# Smart_Mic_V01.net
KiCad netlist of a schematic drawn in EAGLE
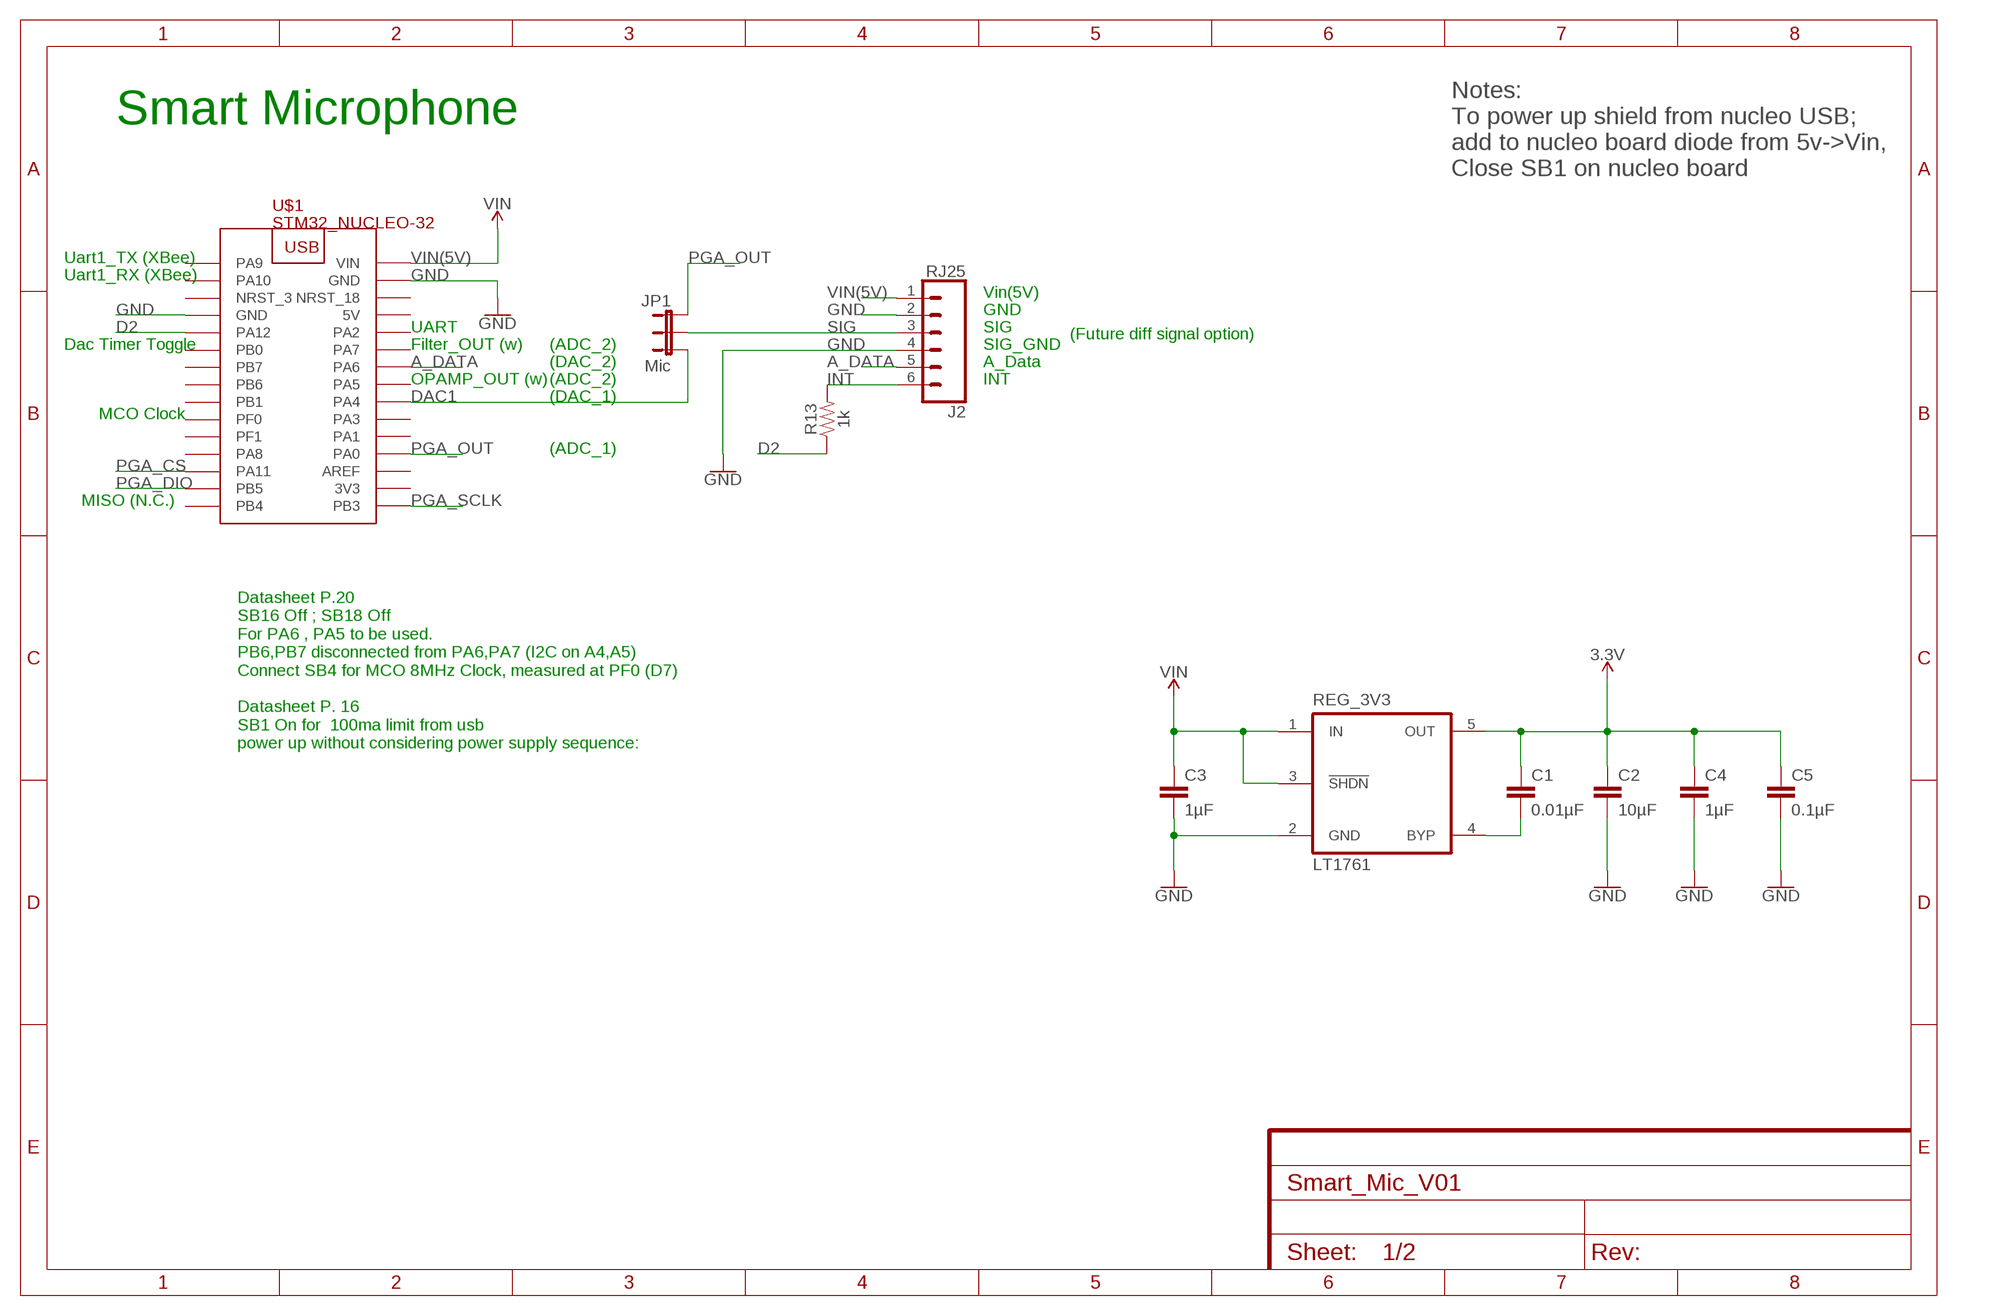
[diagram p0: schematic, sheet 1]
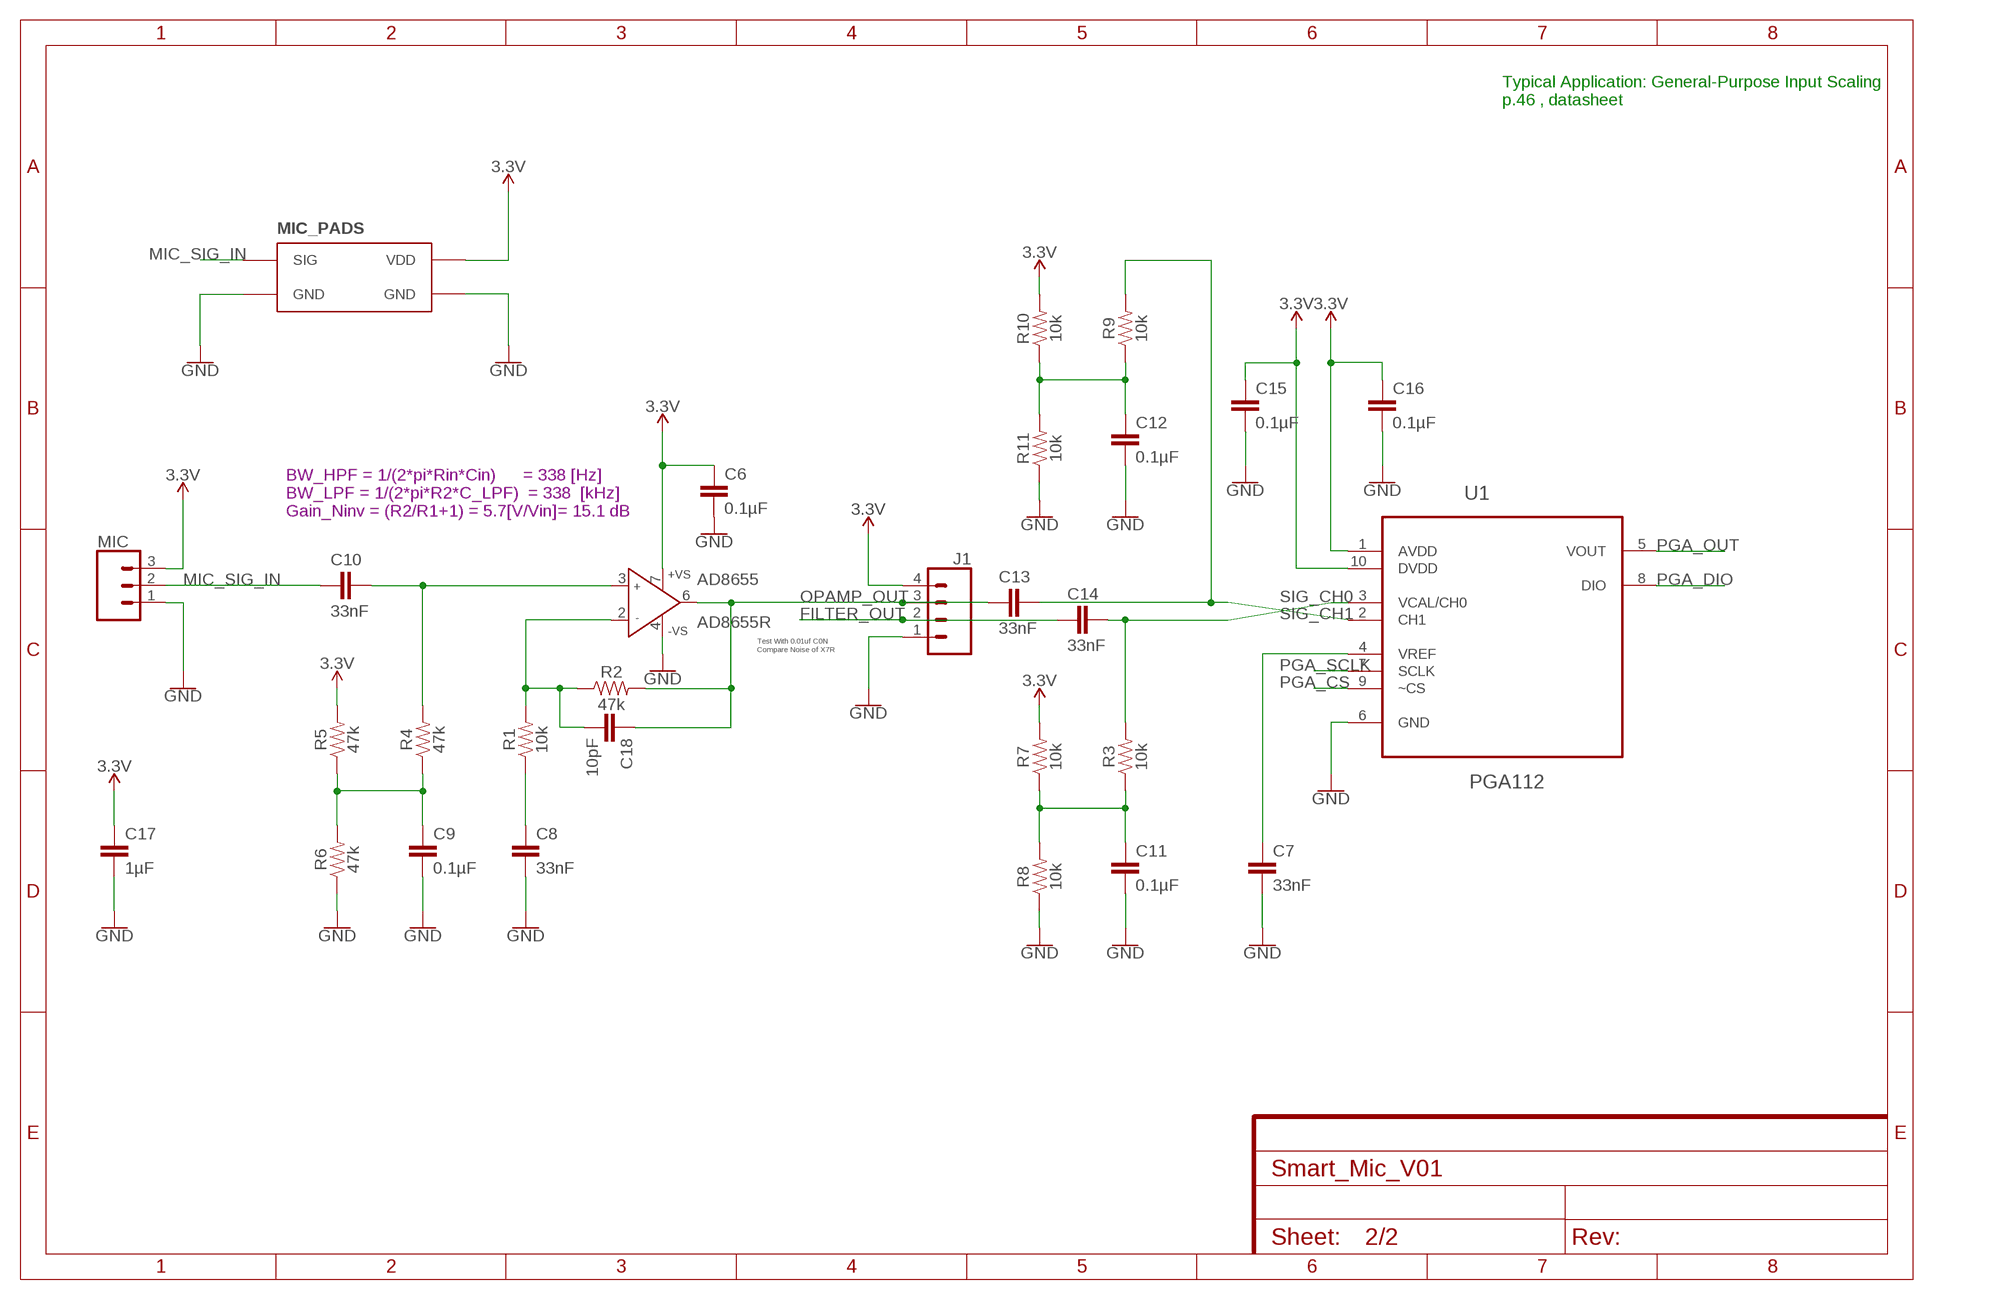
[diagram p1: schematic, sheet 2]

(export (version "E")
  (design (tool "Eeschema 10.0.6"))
  (components
    (comp (ref "C1")
      (value "0.01µF")
      (footprint "eagle-import:0805")
      (libsource (lib "eagle-import") (part "0.33UF/330NF-0805-50V-10%"))
    )
    (comp (ref "C2")
      (value "10µF")
      (footprint "eagle-import:0805")
      (libsource (lib "eagle-import") (part "0.33UF/330NF-0805-50V-10%"))
    )
    (comp (ref "C3")
      (value "1µF")
      (footprint "eagle-import:0805")
      (libsource (lib "eagle-import") (part "0.33UF/330NF-0805-50V-10%"))
    )
    (comp (ref "C4")
      (value "1µF")
      (footprint "eagle-import:0805")
      (libsource (lib "eagle-import") (part "0.33UF/330NF-0805-50V-10%"))
    )
    (comp (ref "C5")
      (value "0.1µF")
      (footprint "eagle-import:0805")
      (libsource (lib "eagle-import") (part "0.33UF/330NF-0805-50V-10%"))
    )
    (comp (ref "J2")
      (value "RJ25")
      (footprint "eagle-import:RJ11-6")
      (libsource (lib "eagle-import") (part "RJ11-6"))
    )
    (comp (ref "JP1")
      (value "Mic")
      (footprint "eagle-import:1X03")
      (libsource (lib "eagle-import") (part "JUMPER-3PTH"))
    )
    (comp (ref "R13")
      (value "1k")
      (footprint "eagle-import:0805")
      (libsource (lib "eagle-import") (part "RESISTOR0805"))
    )
    (comp (ref "REG_3V3")
      (value "LT1761")
      (footprint "eagle-import:SOT23-5")
      (libsource (lib "eagle-import") (part "LT1761"))
    )
    (comp (ref "U$1")
      (value "STM32_NUCLEO-32")
      (footprint "eagle-import:STM32_NUCLEO-32")
      (libsource (lib "eagle-import") (part "STM32_NUCLEO-32"))
    )
    (comp (ref "AD8655")
      (value "AD8655R")
      (footprint "eagle-import:SO8")
      (fields (field (name "MF") "ALTERA CORPORATION") (field (name "MPN") "AD8655ARMZ-REEL"))
      (libsource (lib "eagle-import") (part "AD8655R"))
    )
    (comp (ref "C6")
      (value "0.1µF")
      (footprint "eagle-import:0805")
      (libsource (lib "eagle-import") (part "0.33UF/330NF-0805-50V-10%"))
    )
    (comp (ref "C7")
      (value "33nF")
      (footprint "eagle-import:0805")
      (libsource (lib "eagle-import") (part "0.33UF/330NF-0805-50V-10%"))
    )
    (comp (ref "C8")
      (value "33nF")
      (footprint "eagle-import:0805")
      (libsource (lib "eagle-import") (part "0.33UF/330NF-0805-50V-10%"))
    )
    (comp (ref "C9")
      (value "0.1µF")
      (footprint "eagle-import:0805")
      (libsource (lib "eagle-import") (part "0.33UF/330NF-0805-50V-10%"))
    )
    (comp (ref "C10")
      (value "33nF")
      (footprint "eagle-import:0805")
      (libsource (lib "eagle-import") (part "0.33UF/330NF-0805-50V-10%"))
    )
    (comp (ref "C11")
      (value "0.1µF")
      (footprint "eagle-import:0805")
      (libsource (lib "eagle-import") (part "0.33UF/330NF-0805-50V-10%"))
    )
    (comp (ref "C12")
      (value "0.1µF")
      (footprint "eagle-import:0805")
      (libsource (lib "eagle-import") (part "0.33UF/330NF-0805-50V-10%"))
    )
    (comp (ref "C13")
      (value "33nF")
      (footprint "eagle-import:0805")
      (libsource (lib "eagle-import") (part "0.33UF/330NF-0805-50V-10%"))
    )
    (comp (ref "C14")
      (value "33nF")
      (footprint "eagle-import:0805")
      (libsource (lib "eagle-import") (part "0.33UF/330NF-0805-50V-10%"))
    )
    (comp (ref "C15")
      (value "0.1µF")
      (footprint "eagle-import:0805")
      (libsource (lib "eagle-import") (part "0.33UF/330NF-0805-50V-10%"))
    )
    (comp (ref "C16")
      (value "0.1µF")
      (footprint "eagle-import:0805")
      (libsource (lib "eagle-import") (part "0.33UF/330NF-0805-50V-10%"))
    )
    (comp (ref "C17")
      (value "1µF")
      (footprint "eagle-import:0805")
      (libsource (lib "eagle-import") (part "0.33UF/330NF-0805-50V-10%"))
    )
    (comp (ref "C18")
      (value "10pF")
      (footprint "eagle-import:0805")
      (libsource (lib "eagle-import") (part "0.33UF/330NF-0805-50V-10%"))
    )
    (comp (ref "J1")
      (value "CONN_04")
      (footprint "eagle-import:1X04")
      (libsource (lib "eagle-import") (part "CONN_04"))
    )
    (comp (ref "MIC")
      (value "CONN_03")
      (footprint "eagle-import:1X03")
      (libsource (lib "eagle-import") (part "CONN_03"))
    )
    (comp (ref "R1")
      (value "10k")
      (footprint "eagle-import:0805")
      (libsource (lib "eagle-import") (part "RESISTOR0805"))
    )
    (comp (ref "R2")
      (value "47k")
      (footprint "eagle-import:0805")
      (libsource (lib "eagle-import") (part "RESISTOR0805"))
    )
    (comp (ref "R3")
      (value "10k")
      (footprint "eagle-import:0805")
      (libsource (lib "eagle-import") (part "RESISTOR0805"))
    )
    (comp (ref "R4")
      (value "47k")
      (footprint "eagle-import:0805")
      (libsource (lib "eagle-import") (part "RESISTOR0805"))
    )
    (comp (ref "R5")
      (value "47k")
      (footprint "eagle-import:0805")
      (libsource (lib "eagle-import") (part "RESISTOR0805"))
    )
    (comp (ref "R6")
      (value "47k")
      (footprint "eagle-import:0805")
      (libsource (lib "eagle-import") (part "RESISTOR0805"))
    )
    (comp (ref "R7")
      (value "10k")
      (footprint "eagle-import:0805")
      (libsource (lib "eagle-import") (part "RESISTOR0805"))
    )
    (comp (ref "R8")
      (value "10k")
      (footprint "eagle-import:0805")
      (libsource (lib "eagle-import") (part "RESISTOR0805"))
    )
    (comp (ref "R9")
      (value "10k")
      (footprint "eagle-import:0805")
      (libsource (lib "eagle-import") (part "RESISTOR0805"))
    )
    (comp (ref "R10")
      (value "10k")
      (footprint "eagle-import:0805")
      (libsource (lib "eagle-import") (part "RESISTOR0805"))
    )
    (comp (ref "R11")
      (value "10k")
      (footprint "eagle-import:0805")
      (libsource (lib "eagle-import") (part "RESISTOR0805"))
    )
    (comp (ref "U$2")
      (value "MIC_PADS")
      (footprint "eagle-import:MIC_PADS")
      (libsource (lib "eagle-import") (part "MIC_PADS"))
    )
    (comp (ref "U1")
      (value "PGA112")
      (footprint "eagle-import:SOP50P490X110-10N")
      (fields (field (name "MPN") "PGA113AIDGST"))
      (libsource (lib "eagle-import") (part "PGA113AIDGST"))
    )
  )
  (nets
    (net (code "1") (name "3.3V") (class "Default")
      (node (ref "AD8655") (pin "7") (pinfunction "+VS_7") (pintype "input"))
      (node (ref "C1") (pin "1") (pinfunction "1_1") (pintype "passive"))
      (node (ref "C15") (pin "1") (pinfunction "1_1") (pintype "passive"))
      (node (ref "C16") (pin "1") (pinfunction "1_1") (pintype "passive"))
      (node (ref "C17") (pin "1") (pinfunction "1_1") (pintype "passive"))
      (node (ref "C2") (pin "1") (pinfunction "1_1") (pintype "passive"))
      (node (ref "C4") (pin "1") (pinfunction "1_1") (pintype "passive"))
      (node (ref "C5") (pin "1") (pinfunction "1_1") (pintype "passive"))
      (node (ref "C6") (pin "1") (pinfunction "1_1") (pintype "passive"))
      (node (ref "J1") (pin "4") (pinfunction "4_4") (pintype "passive"))
      (node (ref "MIC") (pin "3") (pinfunction "3_3") (pintype "passive"))
      (node (ref "R10") (pin "2") (pinfunction "2_2") (pintype "passive"))
      (node (ref "R5") (pin "2") (pinfunction "2_2") (pintype "passive"))
      (node (ref "R7") (pin "2") (pinfunction "2_2") (pintype "passive"))
      (node (ref "REG_3V3") (pin "5") (pinfunction "OUT_5") (pintype "bidirectional"))
      (node (ref "U$2") (pin "VDD") (pinfunction "VDD_VDD") (pintype "bidirectional"))
      (node (ref "U1") (pin "1") (pinfunction "AVDD_1") (pintype "power_in"))
      (node (ref "U1") (pin "10") (pinfunction "DVDD_10") (pintype "power_in"))
    )
    (net (code "2") (name "3V3") (class "Default")
      (node (ref "U$1") (pin "3V3") (pinfunction "3V3_3V3") (pintype "power_in"))
    )
    (net (code "3") (name "5V") (class "Default")
      (node (ref "U$1") (pin "5V") (pinfunction "5V_5V") (pintype "power_in"))
    )
    (net (code "4") (name "A_DATA") (class "Default")
      (node (ref "J2") (pin "5") (pinfunction "5_5") (pintype "passive"))
      (node (ref "U$1") (pin "PA6") (pinfunction "PA6_PA6") (pintype "bidirectional"))
    )
    (net (code "5") (name "D2") (class "Default")
      (node (ref "R13") (pin "1") (pinfunction "1_1") (pintype "passive"))
      (node (ref "U$1") (pin "PA12") (pinfunction "PA12_PA12") (pintype "bidirectional"))
    )
    (net (code "6") (name "DAC1") (class "Default")
      (node (ref "JP1") (pin "3") (pinfunction "3_3") (pintype "passive"))
      (node (ref "U$1") (pin "PA4") (pinfunction "PA4_PA4") (pintype "bidirectional"))
    )
    (net (code "7") (name "FILTER_OUT") (class "Default")
      (node (ref "C14") (pin "2") (pinfunction "2_2") (pintype "passive"))
      (node (ref "J1") (pin "2") (pinfunction "2_2") (pintype "passive"))
    )
    (net (code "8") (name "GND") (class "Default")
      (node (ref "AD8655") (pin "4") (pinfunction "-VS_4") (pintype "input"))
      (node (ref "C11") (pin "2") (pinfunction "2_2") (pintype "passive"))
      (node (ref "C12") (pin "2") (pinfunction "2_2") (pintype "passive"))
      (node (ref "C15") (pin "2") (pinfunction "2_2") (pintype "passive"))
      (node (ref "C16") (pin "2") (pinfunction "2_2") (pintype "passive"))
      (node (ref "C17") (pin "2") (pinfunction "2_2") (pintype "passive"))
      (node (ref "C2") (pin "2") (pinfunction "2_2") (pintype "passive"))
      (node (ref "C3") (pin "2") (pinfunction "2_2") (pintype "passive"))
      (node (ref "C4") (pin "2") (pinfunction "2_2") (pintype "passive"))
      (node (ref "C5") (pin "2") (pinfunction "2_2") (pintype "passive"))
      (node (ref "C6") (pin "2") (pinfunction "2_2") (pintype "passive"))
      (node (ref "C7") (pin "2") (pinfunction "2_2") (pintype "passive"))
      (node (ref "C8") (pin "2") (pinfunction "2_2") (pintype "passive"))
      (node (ref "C9") (pin "2") (pinfunction "2_2") (pintype "passive"))
      (node (ref "J1") (pin "1") (pinfunction "1_1") (pintype "passive"))
      (node (ref "J2") (pin "2") (pinfunction "2_2") (pintype "passive"))
      (node (ref "J2") (pin "4") (pinfunction "4_4") (pintype "passive"))
      (node (ref "MIC") (pin "1") (pinfunction "1_1") (pintype "passive"))
      (node (ref "R11") (pin "1") (pinfunction "1_1") (pintype "passive"))
      (node (ref "R6") (pin "1") (pinfunction "1_1") (pintype "passive"))
      (node (ref "R8") (pin "1") (pinfunction "1_1") (pintype "passive"))
      (node (ref "REG_3V3") (pin "2") (pinfunction "GND_2") (pintype "bidirectional"))
      (node (ref "U$1") (pin "GND@17") (pinfunction "GND_GND@17") (pintype "power_in"))
      (node (ref "U$1") (pin "GND@4") (pinfunction "GND_GND@4") (pintype "power_in"))
      (node (ref "U$2") (pin "GND$2") (pinfunction "GND_GND$2") (pintype "bidirectional"))
      (node (ref "U$2") (pin "GND$4") (pinfunction "GND_GND$4") (pintype "bidirectional"))
      (node (ref "U1") (pin "6") (pinfunction "GND_6") (pintype "passive"))
    )
    (net (code "9") (name "INT") (class "Default")
      (node (ref "J2") (pin "6") (pinfunction "6_6") (pintype "passive"))
      (node (ref "R13") (pin "2") (pinfunction "2_2") (pintype "passive"))
    )
    (net (code "10") (name "MIC_SIG_IN") (class "Default")
      (node (ref "C10") (pin "2") (pinfunction "2_2") (pintype "passive"))
      (node (ref "MIC") (pin "2") (pinfunction "2_2") (pintype "passive"))
      (node (ref "U$2") (pin "SIG") (pinfunction "SIG_SIG") (pintype "bidirectional"))
    )
    (net (code "11") (name "Net-(AD8655-IN+)") (class "Default")
      (node (ref "AD8655") (pin "3") (pinfunction "IN+_3") (pintype "input"))
      (node (ref "C10") (pin "1") (pinfunction "1_1") (pintype "passive"))
      (node (ref "R4") (pin "2") (pinfunction "2_2") (pintype "passive"))
    )
    (net (code "12") (name "Net-(AD8655-IN-)") (class "Default")
      (node (ref "AD8655") (pin "2") (pinfunction "IN-_2") (pintype "input"))
      (node (ref "C18") (pin "2") (pinfunction "2_2") (pintype "passive"))
      (node (ref "R1") (pin "2") (pinfunction "2_2") (pintype "passive"))
      (node (ref "R2") (pin "1") (pinfunction "1_1") (pintype "passive"))
    )
    (net (code "13") (name "Net-(C8-Pad1)") (class "Default")
      (node (ref "C8") (pin "1") (pinfunction "1_1") (pintype "passive"))
      (node (ref "R1") (pin "1") (pinfunction "1_1") (pintype "passive"))
    )
    (net (code "14") (name "Net-(C9-Pad1)") (class "Default")
      (node (ref "C9") (pin "1") (pinfunction "1_1") (pintype "passive"))
      (node (ref "R4") (pin "1") (pinfunction "1_1") (pintype "passive"))
      (node (ref "R5") (pin "1") (pinfunction "1_1") (pintype "passive"))
      (node (ref "R6") (pin "2") (pinfunction "2_2") (pintype "passive"))
    )
    (net (code "15") (name "Net-(C11-Pad1)") (class "Default")
      (node (ref "C11") (pin "1") (pinfunction "1_1") (pintype "passive"))
      (node (ref "R3") (pin "1") (pinfunction "1_1") (pintype "passive"))
      (node (ref "R7") (pin "1") (pinfunction "1_1") (pintype "passive"))
      (node (ref "R8") (pin "2") (pinfunction "2_2") (pintype "passive"))
    )
    (net (code "16") (name "Net-(C12-Pad1)") (class "Default")
      (node (ref "C12") (pin "1") (pinfunction "1_1") (pintype "passive"))
      (node (ref "R10") (pin "1") (pinfunction "1_1") (pintype "passive"))
      (node (ref "R11") (pin "2") (pinfunction "2_2") (pintype "passive"))
      (node (ref "R9") (pin "1") (pinfunction "1_1") (pintype "passive"))
    )
    (net (code "17") (name "Net-(REG_3V3-BYP)") (class "Default")
      (node (ref "C1") (pin "2") (pinfunction "2_2") (pintype "passive"))
      (node (ref "REG_3V3") (pin "4") (pinfunction "BYP_4") (pintype "bidirectional"))
    )
    (net (code "18") (name "Net-(U1-VREF)") (class "Default")
      (node (ref "C7") (pin "1") (pinfunction "1_1") (pintype "passive"))
      (node (ref "U1") (pin "4") (pinfunction "VREF_4") (pintype "input"))
    )
    (net (code "19") (name "OPAMP_OUT") (class "Default")
      (node (ref "AD8655") (pin "6") (pinfunction "OUT_6") (pintype "output"))
      (node (ref "C13") (pin "2") (pinfunction "2_2") (pintype "passive"))
      (node (ref "C18") (pin "1") (pinfunction "1_1") (pintype "passive"))
      (node (ref "J1") (pin "3") (pinfunction "3_3") (pintype "passive"))
      (node (ref "R2") (pin "2") (pinfunction "2_2") (pintype "passive"))
    )
    (net (code "20") (name "PGA_CS") (class "Default")
      (node (ref "U$1") (pin "PA11") (pinfunction "PA11_PA11") (pintype "bidirectional"))
      (node (ref "U1") (pin "9") (pinfunction "~{CS}_9") (pintype "input"))
    )
    (net (code "21") (name "PGA_DIO") (class "Default")
      (node (ref "U$1") (pin "PB5") (pinfunction "PB5_PB5") (pintype "bidirectional"))
      (node (ref "U1") (pin "8") (pinfunction "DIO_8") (pintype "bidirectional"))
    )
    (net (code "22") (name "PGA_OUT") (class "Default")
      (node (ref "JP1") (pin "1") (pinfunction "1_1") (pintype "passive"))
      (node (ref "U$1") (pin "PA0") (pinfunction "PA0_PA0") (pintype "bidirectional"))
      (node (ref "U1") (pin "5") (pinfunction "VOUT_5") (pintype "output"))
    )
    (net (code "23") (name "PGA_SCLK") (class "Default")
      (node (ref "U$1") (pin "PB3") (pinfunction "PB3_PB3") (pintype "bidirectional"))
      (node (ref "U1") (pin "7") (pinfunction "SCLK_7") (pintype "input"))
    )
    (net (code "24") (name "SIG") (class "Default")
      (node (ref "J2") (pin "3") (pinfunction "3_3") (pintype "passive"))
      (node (ref "JP1") (pin "2") (pinfunction "2_2") (pintype "passive"))
    )
    (net (code "25") (name "SIG_CH0") (class "Default")
      (node (ref "C13") (pin "1") (pinfunction "1_1") (pintype "passive"))
      (node (ref "R9") (pin "2") (pinfunction "2_2") (pintype "passive"))
      (node (ref "U1") (pin "2") (pinfunction "CH1_2") (pintype "input"))
    )
    (net (code "26") (name "SIG_CH1") (class "Default")
      (node (ref "C14") (pin "1") (pinfunction "1_1") (pintype "passive"))
      (node (ref "R3") (pin "2") (pinfunction "2_2") (pintype "passive"))
      (node (ref "U1") (pin "3") (pinfunction "VCAL/CH0_3") (pintype "input"))
    )
    (net (code "27") (name "VIN(5V)") (class "Default")
      (node (ref "C3") (pin "1") (pinfunction "1_1") (pintype "passive"))
      (node (ref "J2") (pin "1") (pinfunction "1_1") (pintype "passive"))
      (node (ref "REG_3V3") (pin "1") (pinfunction "IN_1") (pintype "bidirectional"))
      (node (ref "REG_3V3") (pin "3") (pinfunction "~{SHDN}_3") (pintype "bidirectional"))
      (node (ref "U$1") (pin "VIN") (pinfunction "VIN_VIN") (pintype "power_in"))
    )
    (net (code "28") (name "unconnected-(U$1-PadAREF)") (class "Default")
      (node (ref "U$1") (pin "AREF") (pinfunction "AREF_AREF") (pintype "bidirectional"))
    )
    (net (code "29") (name "unconnected-(U$1-PadNRST_3)") (class "Default")
      (node (ref "U$1") (pin "NRST_3") (pinfunction "NRST_3_NRST_3") (pintype "bidirectional"))
    )
    (net (code "30") (name "unconnected-(U$1-PadNRST_18)") (class "Default")
      (node (ref "U$1") (pin "NRST_18") (pinfunction "NRST_18_NRST_18") (pintype "bidirectional"))
    )
    (net (code "31") (name "unconnected-(U$1-PadPA1)") (class "Default")
      (node (ref "U$1") (pin "PA1") (pinfunction "PA1_PA1") (pintype "bidirectional"))
    )
    (net (code "32") (name "unconnected-(U$1-PadPA2)") (class "Default")
      (node (ref "U$1") (pin "PA2") (pinfunction "PA2_PA2") (pintype "bidirectional"))
    )
    (net (code "33") (name "unconnected-(U$1-PadPA3)") (class "Default")
      (node (ref "U$1") (pin "PA3") (pinfunction "PA3_PA3") (pintype "bidirectional"))
    )
    (net (code "34") (name "unconnected-(U$1-PadPA5)") (class "Default")
      (node (ref "U$1") (pin "PA5") (pinfunction "PA5_PA5") (pintype "bidirectional"))
    )
    (net (code "35") (name "unconnected-(U$1-PadPA7)") (class "Default")
      (node (ref "U$1") (pin "PA7") (pinfunction "PA7_PA7") (pintype "bidirectional"))
    )
    (net (code "36") (name "unconnected-(U$1-PadPA8)") (class "Default")
      (node (ref "U$1") (pin "PA8") (pinfunction "PA8_PA8") (pintype "bidirectional"))
    )
    (net (code "37") (name "unconnected-(U$1-PadPA9)") (class "Default")
      (node (ref "U$1") (pin "PA9") (pinfunction "PA9_PA9") (pintype "bidirectional"))
    )
    (net (code "38") (name "unconnected-(U$1-PadPA10)") (class "Default")
      (node (ref "U$1") (pin "PA10") (pinfunction "PA10_PA10") (pintype "bidirectional"))
    )
    (net (code "39") (name "unconnected-(U$1-PadPB0)") (class "Default")
      (node (ref "U$1") (pin "PB0") (pinfunction "PB0_PB0") (pintype "bidirectional"))
    )
    (net (code "40") (name "unconnected-(U$1-PadPB1)") (class "Default")
      (node (ref "U$1") (pin "PB1") (pinfunction "PB1_PB1") (pintype "bidirectional"))
    )
    (net (code "41") (name "unconnected-(U$1-PadPB4)") (class "Default")
      (node (ref "U$1") (pin "PB4") (pinfunction "PB4_PB4") (pintype "bidirectional"))
    )
    (net (code "42") (name "unconnected-(U$1-PadPB6)") (class "Default")
      (node (ref "U$1") (pin "PB6") (pinfunction "PB6_PB6") (pintype "bidirectional"))
    )
    (net (code "43") (name "unconnected-(U$1-PadPB7)") (class "Default")
      (node (ref "U$1") (pin "PB7") (pinfunction "PB7_PB7") (pintype "bidirectional"))
    )
    (net (code "44") (name "unconnected-(U$1-PadPF0)") (class "Default")
      (node (ref "U$1") (pin "PF0") (pinfunction "PF0_PF0") (pintype "bidirectional"))
    )
    (net (code "45") (name "unconnected-(U$1-PadPF1)") (class "Default")
      (node (ref "U$1") (pin "PF1") (pinfunction "PF1_PF1") (pintype "bidirectional"))
    )
  )
)
